# PAGE1.net
KiCad netlist of a schematic drawn in Altium Designer
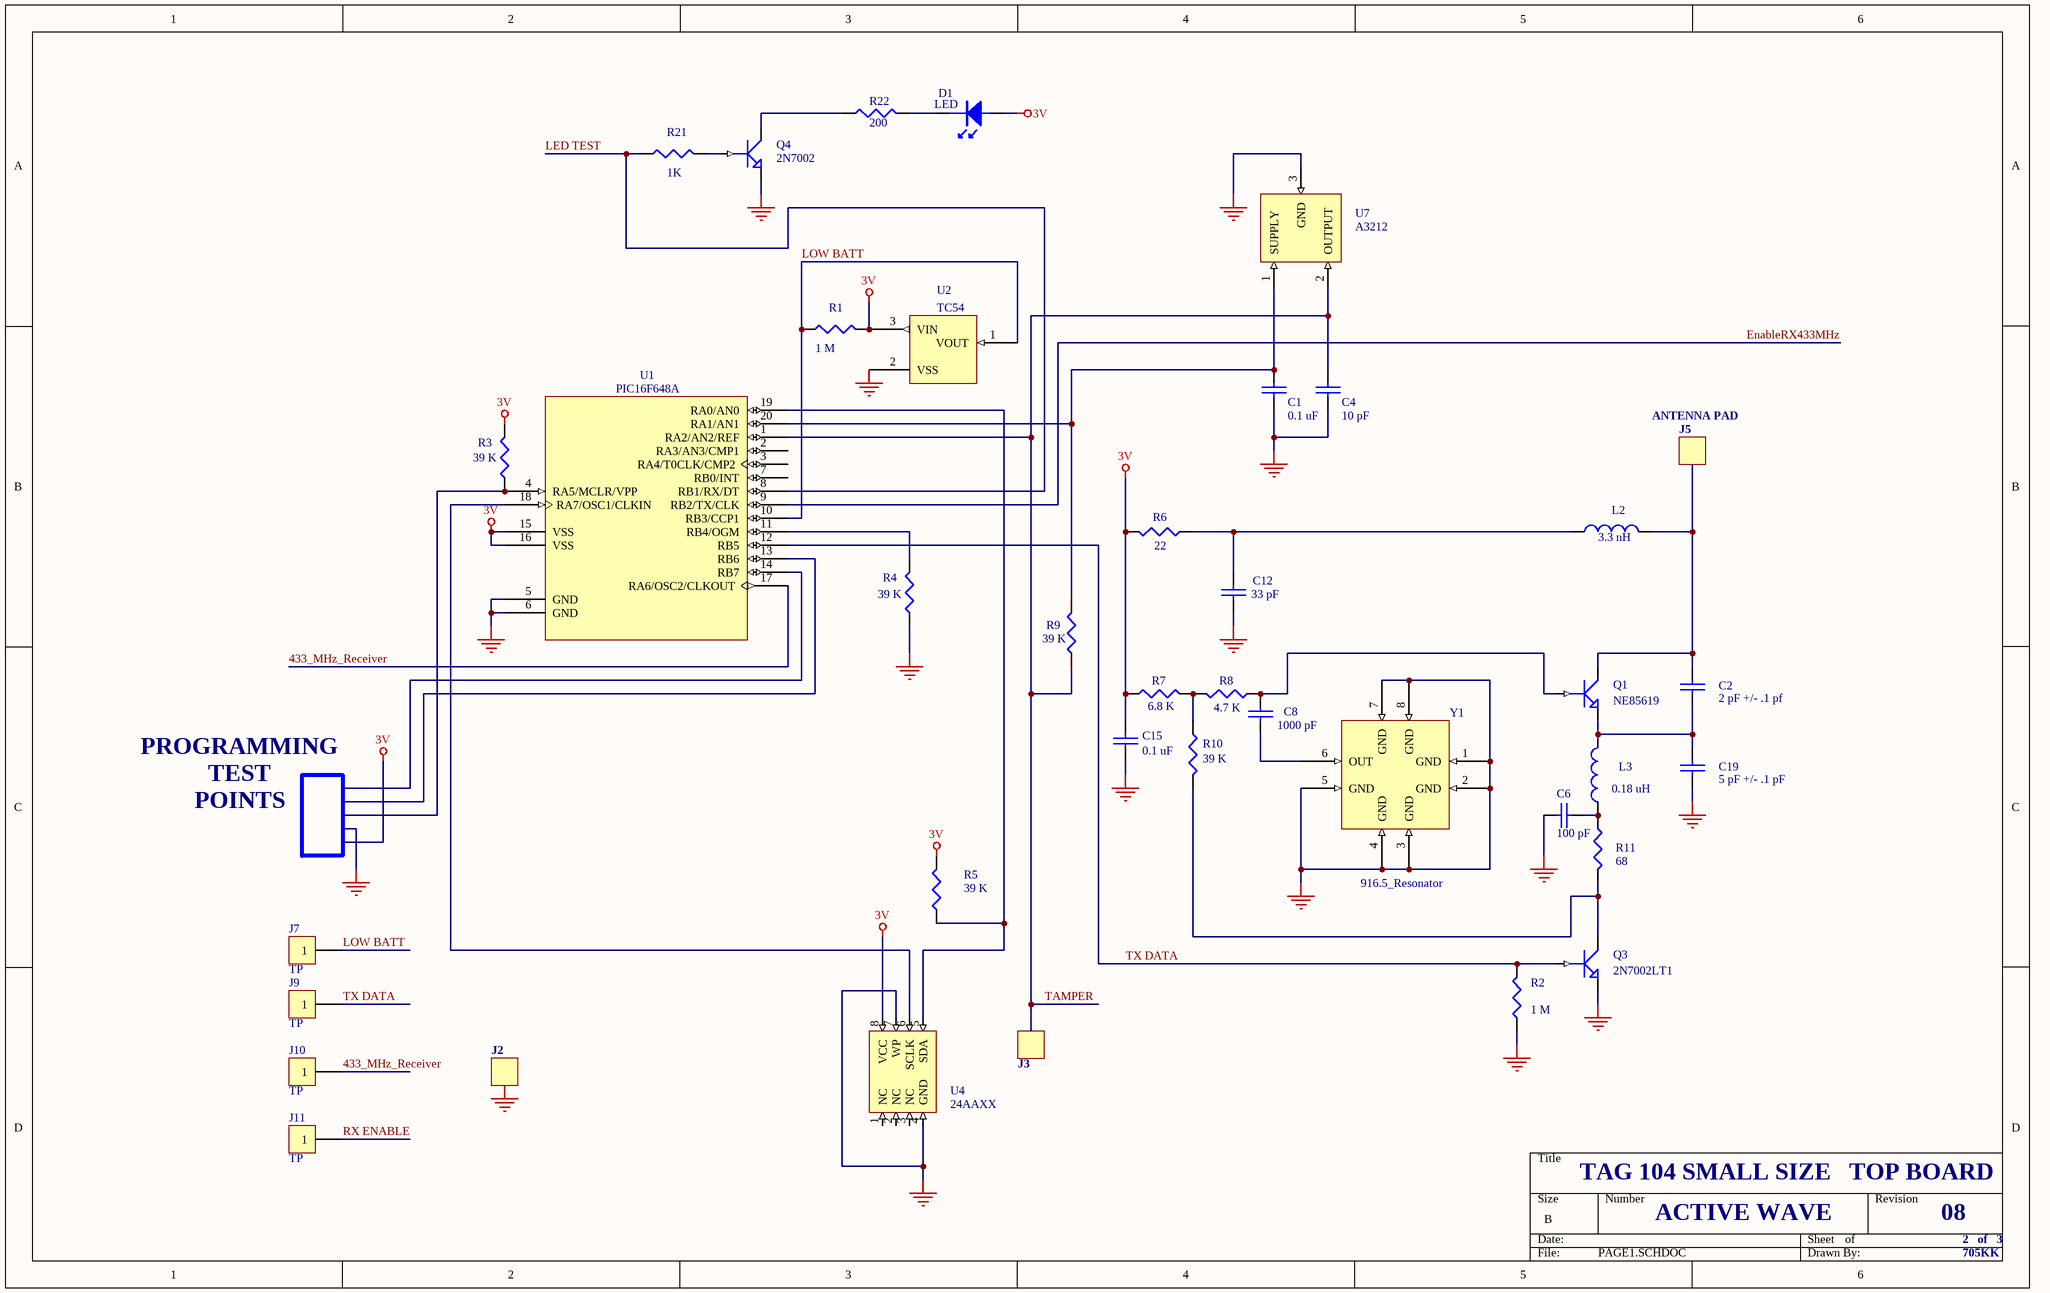
[diagram p0: PAGE1.SCHDOC]

(export (version "E")
  (design (tool "Eeschema 10.0.6"))
  (components
    (comp (ref "C1")
      (value "0.1 uF")
      (footprint "0603")
      (description "Capacitor")
      (libsource (lib "*") (part "CAP"))
    )
    (comp (ref "C2")
      (value "2 pF +/- .1 pf")
      (footprint "0603")
      (description "Capacitor")
      (libsource (lib "*") (part "CAP"))
    )
    (comp (ref "C4")
      (value "10 pF")
      (footprint "0603")
      (description "Capacitor")
      (libsource (lib "*") (part "CAP"))
    )
    (comp (ref "C6")
      (value "100 pF")
      (footprint "0603")
      (description "Capacitor")
      (libsource (lib "*") (part "CAP"))
    )
    (comp (ref "C8")
      (value "1000 pF")
      (footprint "0603")
      (description "Capacitor")
      (libsource (lib "*") (part "CAP"))
    )
    (comp (ref "C12")
      (value "33 pF")
      (footprint "0603")
      (description "Capacitor")
      (libsource (lib "*") (part "CAP"))
    )
    (comp (ref "C15")
      (value "0.1 uF")
      (footprint "0603")
      (description "Capacitor")
      (libsource (lib "*") (part "CAP"))
    )
    (comp (ref "C19")
      (value "5 pF +/- .1 pF")
      (footprint "0603")
      (description "Capacitor")
      (libsource (lib "*") (part "CAP"))
    )
    (comp (ref "D1") (value "LED") (footprint "LED STANLEY H_1105W") (libsource (lib "*") (part "LED")))
    (comp (ref "J7")
      (value "TP")
      (footprint "TEST POINT PAD 5")
      (description "Connector")
      (libsource (lib "*") (part "CON1"))
    )
    (comp (ref "J9")
      (value "TP")
      (footprint "TEST POINT PAD 5")
      (description "Connector")
      (libsource (lib "*") (part "CON1"))
    )
    (comp (ref "J10")
      (value "TP")
      (footprint "TEST POINT PAD 5")
      (description "Connector")
      (libsource (lib "*") (part "CON1"))
    )
    (comp (ref "J11")
      (value "TP")
      (footprint "TEST POINT PAD 5")
      (description "Connector")
      (libsource (lib "*") (part "CON1"))
    )
    (comp (ref "L2") (value "3.3 nH") (footprint "0603") (libsource (lib "*") (part "INDUCTOR")))
    (comp (ref "L3") (value "0.18 uH") (footprint "0603") (libsource (lib "*") (part "INDUCTOR")))
    (comp (ref "Q1")
      (value "NE85619")
      (footprint "3 PIN ULTRA SUPER MINI MOLD")
      (description "NPN Transistor")
      (libsource (lib "*") (part "NPN1"))
    )
    (comp (ref "Q3")
      (value "2N7002LT1")
      (footprint "SOT23 TRANS")
      (description "NPN Transistor")
      (libsource (lib "*") (part "NPN1"))
    )
    (comp (ref "Q4")
      (value "2N7002")
      (footprint "SOT23 TRANS")
      (description "NPN Transistor")
      (libsource (lib "*") (part "NPN1"))
    )
    (comp (ref "R1") (value "1 M") (footprint "0603") (libsource (lib "*") (part "RESISTOR")))
    (comp (ref "R2") (value "1 M") (footprint "0603") (libsource (lib "*") (part "RESISTOR")))
    (comp (ref "R3") (value "39 K") (footprint "0603") (libsource (lib "*") (part "RESISTOR")))
    (comp (ref "R4") (value "39 K") (footprint "0603") (libsource (lib "*") (part "RESISTOR")))
    (comp (ref "R5") (value "39 K") (footprint "0603") (libsource (lib "*") (part "RESISTOR")))
    (comp (ref "R6") (value "22") (footprint "0603") (libsource (lib "*") (part "RESISTOR")))
    (comp (ref "R7") (value "6.8 K") (footprint "0603") (libsource (lib "*") (part "RESISTOR")))
    (comp (ref "R8") (value "4.7 K") (footprint "0603") (libsource (lib "*") (part "RESISTOR")))
    (comp (ref "R9") (value "39 K") (footprint "0603") (libsource (lib "*") (part "RESISTOR")))
    (comp (ref "R10") (value "39 K") (footprint "0603") (libsource (lib "*") (part "RESISTOR")))
    (comp (ref "R11") (value "68") (footprint "0603") (libsource (lib "*") (part "RES1")))
    (comp (ref "R21") (value "1K") (footprint "0603") (libsource (lib "*") (part "RESISTOR")))
    (comp (ref "R22") (value "200") (footprint "0603") (libsource (lib "*") (part "RES1")))
    (comp (ref "U1")
      (value "PIC16F648A")
      (footprint "SSOP20 WIDE")
      (libsource (lib "*") (part "PIC16F68A/SSOP"))
    )
    (comp (ref "U2") (value "TC54") (footprint "SOT23") (libsource (lib "*") (part "TC54_1")))
    (comp (ref "U4") (value "24AAXX") (footprint "SO8") (libsource (lib "*") (part "24AA256")))
    (comp (ref "U7") (value "A3212") (footprint "SOT23W") (libsource (lib "*") (part "HALL EFFECT SWITCH")))
    (comp (ref "Y1")
      (value "916.5_Resonator")
      (footprint "RESONATOR")
      (libsource (lib "*") (part "RESONATOR"))
    )
  )
  (nets
    (net (code "1") (name "/433_MHz_Receiver") (class "Default")
      (node (ref "J10") (pin "1") (pinfunction "1_1") (pintype "passive"))
      (node (ref "U1") (pin "17") (pinfunction "RA6/OSC2/CLKOUT_17") (pintype "output"))
    )
    (net (code "2") (name "/EnableRX433MHz") (class "Default")
      (node (ref "U1") (pin "9") (pinfunction "RB2/TX/CLK_9") (pintype "bidirectional"))
    )
    (net (code "3") (name "/LED TEST") (class "Default")
      (node (ref "R21") (pin "1") (pinfunction "1_1") (pintype "passive"))
      (node (ref "U1") (pin "8") (pinfunction "RB1/RX/DT_8") (pintype "bidirectional"))
    )
    (net (code "4") (name "/LOW BATT") (class "Default")
      (node (ref "J7") (pin "1") (pinfunction "1_1") (pintype "passive"))
      (node (ref "R1") (pin "1") (pinfunction "1_1") (pintype "passive"))
      (node (ref "U1") (pin "10") (pinfunction "RB3/CCP1_10") (pintype "bidirectional"))
      (node (ref "U2") (pin "1") (pinfunction "VOUT_1") (pintype "input"))
    )
    (net (code "5") (name "/RX ENABLE") (class "Default")
      (node (ref "J11") (pin "1") (pinfunction "1_1") (pintype "passive"))
    )
    (net (code "6") (name "/TAMPER") (class "Default")
      (node (ref "C4") (pin "1") (pinfunction "1_1") (pintype "passive"))
      (node (ref "R9") (pin "1") (pinfunction "1_1") (pintype "passive"))
      (node (ref "U1") (pin "1") (pinfunction "RA2/AN2/REF_1") (pintype "bidirectional"))
      (node (ref "U7") (pin "2") (pinfunction "OUTPUT_2") (pintype "input"))
    )
    (net (code "7") (name "/TX DATA") (class "Default")
      (node (ref "J9") (pin "1") (pinfunction "1_1") (pintype "passive"))
      (node (ref "Q3") (pin "B") (pinfunction "B_B") (pintype "input"))
      (node (ref "R2") (pin "2") (pinfunction "2_2") (pintype "passive"))
      (node (ref "U1") (pin "12") (pinfunction "RB5_12") (pintype "bidirectional"))
    )
    (net (code "8") (name "3V") (class "Default")
      (node (ref "C15") (pin "1") (pinfunction "1_1") (pintype "passive"))
      (node (ref "D1") (pin "A") (pinfunction "A_A") (pintype "passive"))
      (node (ref "R1") (pin "2") (pinfunction "2_2") (pintype "passive"))
      (node (ref "R3") (pin "2") (pinfunction "2_2") (pintype "passive"))
      (node (ref "R5") (pin "2") (pinfunction "2_2") (pintype "passive"))
      (node (ref "R6") (pin "2") (pinfunction "2_2") (pintype "passive"))
      (node (ref "R7") (pin "1") (pinfunction "1_1") (pintype "passive"))
      (node (ref "U1") (pin "15") (pinfunction "VSS_15") (pintype "power_in"))
      (node (ref "U1") (pin "16") (pinfunction "VSS_16") (pintype "power_in"))
      (node (ref "U2") (pin "3") (pinfunction "VIN_3") (pintype "output"))
      (node (ref "U4") (pin "8") (pinfunction "VCC_8") (pintype "input"))
    )
    (net (code "9") (name "GND_SIGNAL") (class "Default")
      (node (ref "C1") (pin "2") (pinfunction "2_2") (pintype "passive"))
      (node (ref "C12") (pin "2") (pinfunction "2_2") (pintype "passive"))
      (node (ref "C15") (pin "2") (pinfunction "2_2") (pintype "passive"))
      (node (ref "C19") (pin "2") (pinfunction "2_2") (pintype "passive"))
      (node (ref "C4") (pin "2") (pinfunction "2_2") (pintype "passive"))
      (node (ref "C6") (pin "1") (pinfunction "1_1") (pintype "passive"))
      (node (ref "Q3") (pin "E") (pinfunction "E_E") (pintype "passive"))
      (node (ref "Q4") (pin "E") (pinfunction "E_E") (pintype "passive"))
      (node (ref "R2") (pin "1") (pinfunction "1_1") (pintype "passive"))
      (node (ref "R4") (pin "1") (pinfunction "1_1") (pintype "passive"))
      (node (ref "U1") (pin "5") (pinfunction "GND_5") (pintype "power_in"))
      (node (ref "U1") (pin "6") (pinfunction "GND_6") (pintype "power_in"))
      (node (ref "U2") (pin "2") (pinfunction "VSS_2") (pintype "power_in"))
      (node (ref "U4") (pin "4") (pinfunction "GND_4") (pintype "input"))
      (node (ref "U4") (pin "7") (pinfunction "WP_7") (pintype "input"))
      (node (ref "U7") (pin "3") (pinfunction "GND_3") (pintype "input"))
      (node (ref "Y1") (pin "1") (pinfunction "GND_1") (pintype "input"))
      (node (ref "Y1") (pin "2") (pinfunction "GND_2") (pintype "input"))
      (node (ref "Y1") (pin "3") (pinfunction "GND_3") (pintype "input"))
      (node (ref "Y1") (pin "4") (pinfunction "GND_4") (pintype "input"))
      (node (ref "Y1") (pin "5") (pinfunction "GND_5") (pintype "input"))
      (node (ref "Y1") (pin "7") (pinfunction "GND_7") (pintype "input"))
      (node (ref "Y1") (pin "8") (pinfunction "GND_8") (pintype "input"))
    )
    (net (code "10") (name "Net-(C2-Pad1)") (class "Default")
      (node (ref "C2") (pin "1") (pinfunction "1_1") (pintype "passive"))
      (node (ref "L2") (pin "2") (pinfunction "2_2") (pintype "passive"))
      (node (ref "Q1") (pin "C") (pinfunction "C_C") (pintype "passive"))
    )
    (net (code "11") (name "Net-(C6-Pad2)") (class "Default")
      (node (ref "C6") (pin "2") (pinfunction "2_2") (pintype "passive"))
      (node (ref "L3") (pin "1") (pinfunction "1_1") (pintype "passive"))
      (node (ref "R11") (pin "1") (pinfunction "1_1") (pintype "passive"))
    )
    (net (code "12") (name "Net-(C8-Pad1)") (class "Default")
      (node (ref "C8") (pin "1") (pinfunction "1_1") (pintype "passive"))
      (node (ref "Q1") (pin "B") (pinfunction "B_B") (pintype "input"))
      (node (ref "R8") (pin "1") (pinfunction "1_1") (pintype "passive"))
    )
    (net (code "13") (name "Net-(C12-Pad1)") (class "Default")
      (node (ref "C12") (pin "1") (pinfunction "1_1") (pintype "passive"))
      (node (ref "L2") (pin "1") (pinfunction "1_1") (pintype "passive"))
      (node (ref "R6") (pin "1") (pinfunction "1_1") (pintype "passive"))
    )
    (net (code "14") (name "Net-(C19-Pad1)") (class "Default")
      (node (ref "C19") (pin "1") (pinfunction "1_1") (pintype "passive"))
      (node (ref "C2") (pin "2") (pinfunction "2_2") (pintype "passive"))
      (node (ref "L3") (pin "2") (pinfunction "2_2") (pintype "passive"))
      (node (ref "Q1") (pin "E") (pinfunction "E_E") (pintype "passive"))
    )
    (net (code "15") (name "Net-(D1-PadK)") (class "Default")
      (node (ref "D1") (pin "K") (pinfunction "K_K") (pintype "passive"))
      (node (ref "R22") (pin "2") (pinfunction "2_2") (pintype "passive"))
    )
    (net (code "16") (name "Net-(Q3-PadC)") (class "Default")
      (node (ref "Q3") (pin "C") (pinfunction "C_C") (pintype "passive"))
      (node (ref "R10") (pin "2") (pinfunction "2_2") (pintype "passive"))
      (node (ref "R11") (pin "2") (pinfunction "2_2") (pintype "passive"))
    )
    (net (code "17") (name "Net-(Q4-PadB)") (class "Default")
      (node (ref "Q4") (pin "B") (pinfunction "B_B") (pintype "input"))
      (node (ref "R21") (pin "2") (pinfunction "2_2") (pintype "passive"))
    )
    (net (code "18") (name "Net-(Q4-PadC)") (class "Default")
      (node (ref "Q4") (pin "C") (pinfunction "C_C") (pintype "passive"))
      (node (ref "R22") (pin "1") (pinfunction "1_1") (pintype "passive"))
    )
    (net (code "19") (name "Net-(R10-Pad1)") (class "Default")
      (node (ref "R10") (pin "1") (pinfunction "1_1") (pintype "passive"))
      (node (ref "R7") (pin "2") (pinfunction "2_2") (pintype "passive"))
      (node (ref "R8") (pin "2") (pinfunction "2_2") (pintype "passive"))
    )
    (net (code "20") (name "Net-(U1-RA0{slash}AN0)") (class "Default")
      (node (ref "R5") (pin "1") (pinfunction "1_1") (pintype "passive"))
      (node (ref "U1") (pin "19") (pinfunction "RA0/AN0_19") (pintype "bidirectional"))
      (node (ref "U4") (pin "5") (pinfunction "SDA_5") (pintype "input"))
    )
    (net (code "21") (name "Net-(U1-RA1{slash}AN1)") (class "Default")
      (node (ref "C1") (pin "1") (pinfunction "1_1") (pintype "passive"))
      (node (ref "R9") (pin "2") (pinfunction "2_2") (pintype "passive"))
      (node (ref "U1") (pin "20") (pinfunction "RA1/AN1_20") (pintype "bidirectional"))
      (node (ref "U7") (pin "1") (pinfunction "SUPPLY_1") (pintype "input"))
    )
    (net (code "22") (name "Net-(U1-RA5{slash}MCLR{slash}VPP)") (class "Default")
      (node (ref "R3") (pin "1") (pinfunction "1_1") (pintype "passive"))
      (node (ref "U1") (pin "4") (pinfunction "RA5/MCLR/VPP_4") (pintype "input"))
    )
    (net (code "23") (name "Net-(U1-RA7{slash}OSC1{slash}CLKIN)") (class "Default")
      (node (ref "U1") (pin "18") (pinfunction "RA7/OSC1/CLKIN_18") (pintype "input"))
      (node (ref "U4") (pin "6") (pinfunction "SCLK_6") (pintype "input"))
    )
    (net (code "24") (name "Net-(U1-RB4{slash}OGM)") (class "Default")
      (node (ref "R4") (pin "2") (pinfunction "2_2") (pintype "passive"))
      (node (ref "U1") (pin "11") (pinfunction "RB4/OGM_11") (pintype "bidirectional"))
    )
    (net (code "25") (name "Net-(Y1-OUT)") (class "Default")
      (node (ref "C8") (pin "2") (pinfunction "2_2") (pintype "passive"))
      (node (ref "Y1") (pin "6") (pinfunction "OUT_6") (pintype "input"))
    )
    (net (code "26") (name "unconnected-(U1-RA3{slash}AN3{slash}CMP1-Pad2)") (class "Default")
      (node (ref "U1") (pin "2") (pinfunction "RA3/AN3/CMP1_2") (pintype "bidirectional"))
    )
    (net (code "27") (name "unconnected-(U1-RA4{slash}T0CLK{slash}CMP2-Pad3)") (class "Default")
      (node (ref "U1") (pin "3") (pinfunction "RA4/T0CLK/CMP2_3") (pintype "bidirectional"))
    )
    (net (code "28") (name "unconnected-(U1-RB0{slash}INT-Pad7)") (class "Default")
      (node (ref "U1") (pin "7") (pinfunction "RB0/INT_7") (pintype "bidirectional"))
    )
    (net (code "29") (name "unconnected-(U1-RB6-Pad13)") (class "Default")
      (node (ref "U1") (pin "13") (pinfunction "RB6_13") (pintype "bidirectional"))
    )
    (net (code "30") (name "unconnected-(U1-RB7-Pad14)") (class "Default")
      (node (ref "U1") (pin "14") (pinfunction "RB7_14") (pintype "bidirectional"))
    )
    (net (code "31") (name "unconnected-(U4-NC-Pad1)") (class "Default")
      (node (ref "U4") (pin "1") (pinfunction "NC_1") (pintype "input"))
    )
    (net (code "32") (name "unconnected-(U4-NC-Pad2)") (class "Default")
      (node (ref "U4") (pin "2") (pinfunction "NC_2") (pintype "input"))
    )
    (net (code "33") (name "unconnected-(U4-NC-Pad3)") (class "Default")
      (node (ref "U4") (pin "3") (pinfunction "NC_3") (pintype "input"))
    )
  )
)
